# TeensyZE.net
KiCad netlist of a schematic drawn in EAGLE
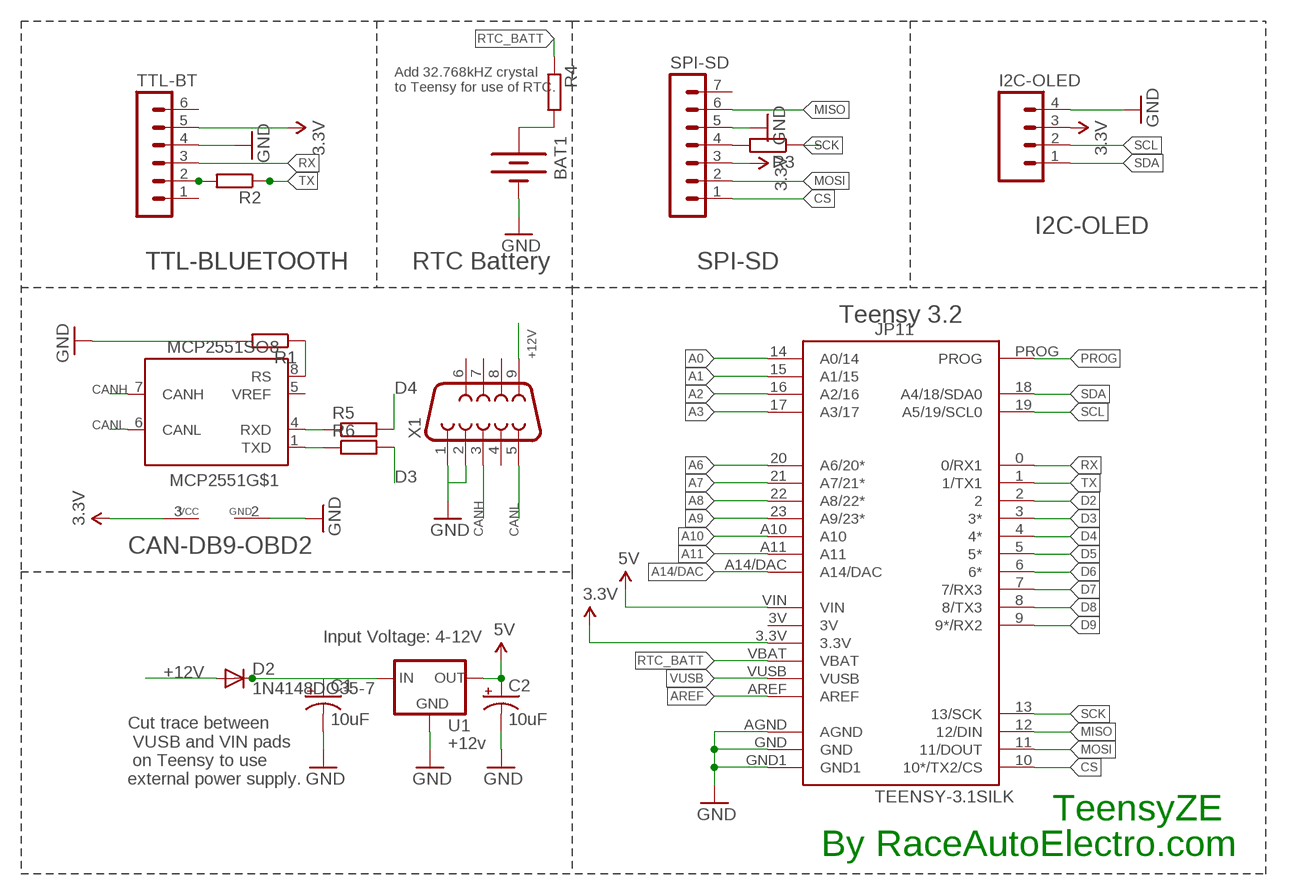
[diagram p0: schematic, sheet 1]

(export (version "E")
  (design (tool "Eeschema 10.0.6"))
  (components
    (comp (ref "BAT1")
      (value "BATTERY12PTH")
      (footprint "eagle-import:BATTCON_12MM_PTH")
      (libsource (lib "eagle-import") (part "BATTERY12PTH"))
    )
    (comp (ref "C1")
      (value "10uF")
      (footprint "eagle-import:CPOL-RADIAL-10UF-25V")
      (libsource (lib "eagle-import") (part "10UF-25V-20%(PTH)"))
    )
    (comp (ref "C2")
      (value "10uF")
      (footprint "eagle-import:CPOL-RADIAL-10UF-25V")
      (libsource (lib "eagle-import") (part "10UF-25V-20%(PTH)"))
    )
    (comp (ref "D2")
      (value "1N4148DO35-7")
      (footprint "eagle-import:DO35-7")
      (libsource (lib "eagle-import") (part "1N4148DO35-7"))
    )
    (comp (ref "I2C-OLED")
      (value "M04PTH")
      (footprint "eagle-import:1X04")
      (libsource (lib "eagle-import") (part "M04PTH"))
    )
    (comp (ref "JP11")
      (value "TEENSY-3.1SILK")
      (footprint "eagle-import:TEENSY-3.1")
      (libsource (lib "eagle-import") (part "TEENSY-3.1SILK"))
    )
    (comp (ref "MCP2551")
      (value "MCP2551SO8")
      (footprint "eagle-import:SO08")
      (libsource (lib "eagle-import") (part "MCP2551SO8"))
    )
    (comp (ref "R1")
      (value "R-EU_R0805")
      (footprint "eagle-import:R0805")
      (libsource (lib "eagle-import") (part "R-EU_R0805"))
    )
    (comp (ref "R2")
      (value "R-EU_R0805")
      (footprint "eagle-import:R0805")
      (libsource (lib "eagle-import") (part "R-EU_R0805"))
    )
    (comp (ref "R3")
      (value "R-EU_R0805")
      (footprint "eagle-import:R0805")
      (libsource (lib "eagle-import") (part "R-EU_R0805"))
    )
    (comp (ref "R4")
      (value "R-EU_R0805")
      (footprint "eagle-import:R0805")
      (libsource (lib "eagle-import") (part "R-EU_R0805"))
    )
    (comp (ref "R5")
      (value "R-EU_R0805")
      (footprint "eagle-import:R0805")
      (libsource (lib "eagle-import") (part "R-EU_R0805"))
    )
    (comp (ref "R6")
      (value "R-EU_R0805")
      (footprint "eagle-import:R0805")
      (libsource (lib "eagle-import") (part "R-EU_R0805"))
    )
    (comp (ref "SPI-SD")
      (value "MA07-1")
      (footprint "eagle-import:MA07-1")
      (libsource (lib "eagle-import") (part "MA07-1"))
    )
    (comp (ref "TTL-BT")
      (value "MA06-1")
      (footprint "eagle-import:MA06-1")
      (libsource (lib "eagle-import") (part "MA06-1"))
    )
    (comp (ref "U1")
      (value "+12v")
      (footprint "eagle-import:TO-252")
      (libsource (lib "eagle-import") (part "V_REG_78XX7812"))
    )
    (comp (ref "X1")
      (value "F09HP")
      (footprint "eagle-import:F09HP")
      (libsource (lib "eagle-import") (part "F09HP"))
    )
  )
  (nets
    (net (code "1") (name "/+12V") (class "Default")
      (node (ref "D2") (pin "A") (pinfunction "A_A") (pintype "passive"))
      (node (ref "X1") (pin "9") (pinfunction "9_9") (pintype "passive"))
    )
    (net (code "2") (name "/CANH") (class "Default")
      (node (ref "MCP2551") (pin "7") (pinfunction "CANH_7") (pintype "bidirectional"))
      (node (ref "X1") (pin "3") (pinfunction "3_3") (pintype "passive"))
    )
    (net (code "3") (name "/CANL") (class "Default")
      (node (ref "MCP2551") (pin "6") (pinfunction "CANL_6") (pintype "bidirectional"))
      (node (ref "X1") (pin "5") (pinfunction "5_5") (pintype "passive"))
    )
    (net (code "4") (name "3.3V") (class "Default")
      (node (ref "I2C-OLED") (pin "3") (pinfunction "3_3") (pintype "passive"))
      (node (ref "JP11") (pin "3.3V") (pinfunction "3.3V_3.3V") (pintype "bidirectional"))
      (node (ref "MCP2551") (pin "3") (pinfunction "VCC_3") (pintype "power_in"))
      (node (ref "SPI-SD") (pin "3") (pinfunction "3_3") (pintype "passive"))
      (node (ref "TTL-BT") (pin "5") (pinfunction "5_5") (pintype "passive"))
    )
    (net (code "5") (name "5V") (class "Default")
      (node (ref "C2") (pin "1") (pinfunction "+_1") (pintype "passive"))
      (node (ref "JP11") (pin "VIN") (pinfunction "VIN_VIN") (pintype "bidirectional"))
      (node (ref "U1") (pin "2") (pinfunction "OUT_2") (pintype "output"))
    )
    (net (code "6") (name "A0") (class "Default")
      (node (ref "JP11") (pin "14") (pinfunction "A0/14_14") (pintype "bidirectional"))
    )
    (net (code "7") (name "A1") (class "Default")
      (node (ref "JP11") (pin "15") (pinfunction "A1/15_15") (pintype "bidirectional"))
    )
    (net (code "8") (name "A2") (class "Default")
      (node (ref "JP11") (pin "16") (pinfunction "A2/16_16") (pintype "bidirectional"))
    )
    (net (code "9") (name "A3") (class "Default")
      (node (ref "JP11") (pin "17") (pinfunction "A3/17_17") (pintype "bidirectional"))
    )
    (net (code "10") (name "A6") (class "Default")
      (node (ref "JP11") (pin "20") (pinfunction "A6/20*_20") (pintype "bidirectional"))
    )
    (net (code "11") (name "A7") (class "Default")
      (node (ref "JP11") (pin "21") (pinfunction "A7/21*_21") (pintype "bidirectional"))
    )
    (net (code "12") (name "A8") (class "Default")
      (node (ref "JP11") (pin "22") (pinfunction "A8/22*_22") (pintype "bidirectional"))
    )
    (net (code "13") (name "A9") (class "Default")
      (node (ref "JP11") (pin "23") (pinfunction "A9/23*_23") (pintype "bidirectional"))
    )
    (net (code "14") (name "A10") (class "Default")
      (node (ref "JP11") (pin "A10") (pinfunction "A10_A10") (pintype "bidirectional"))
    )
    (net (code "15") (name "A11") (class "Default")
      (node (ref "JP11") (pin "A11") (pinfunction "A11_A11") (pintype "bidirectional"))
    )
    (net (code "16") (name "A14{slash}DAC") (class "Default")
      (node (ref "JP11") (pin "A14/DAC") (pinfunction "A14/DAC_A14/DAC") (pintype "bidirectional"))
    )
    (net (code "17") (name "AREF") (class "Default")
      (node (ref "JP11") (pin "AREF") (pinfunction "AREF_AREF") (pintype "bidirectional"))
    )
    (net (code "18") (name "CS") (class "Default")
      (node (ref "JP11") (pin "10") (pinfunction "10*/TX2/CS_10") (pintype "bidirectional"))
      (node (ref "SPI-SD") (pin "1") (pinfunction "1_1") (pintype "passive"))
    )
    (net (code "19") (name "D2") (class "Default")
      (node (ref "JP11") (pin "2") (pinfunction "2_2") (pintype "bidirectional"))
    )
    (net (code "20") (name "D3") (class "Default")
      (node (ref "JP11") (pin "3") (pinfunction "3*_3") (pintype "bidirectional"))
      (node (ref "R6") (pin "2") (pinfunction "2_2") (pintype "passive"))
    )
    (net (code "21") (name "D4") (class "Default")
      (node (ref "JP11") (pin "4") (pinfunction "4*_4") (pintype "bidirectional"))
      (node (ref "R5") (pin "2") (pinfunction "2_2") (pintype "passive"))
    )
    (net (code "22") (name "D5") (class "Default")
      (node (ref "JP11") (pin "5") (pinfunction "5*_5") (pintype "bidirectional"))
    )
    (net (code "23") (name "D6") (class "Default")
      (node (ref "JP11") (pin "6") (pinfunction "6*_6") (pintype "bidirectional"))
    )
    (net (code "24") (name "D7") (class "Default")
      (node (ref "JP11") (pin "7") (pinfunction "7/RX3_7") (pintype "bidirectional"))
    )
    (net (code "25") (name "D8") (class "Default")
      (node (ref "JP11") (pin "8") (pinfunction "8/TX3_8") (pintype "bidirectional"))
    )
    (net (code "26") (name "D9") (class "Default")
      (node (ref "JP11") (pin "9") (pinfunction "9*/RX2_9") (pintype "bidirectional"))
    )
    (net (code "27") (name "GND") (class "Default")
      (node (ref "BAT1") (pin "GND") (pinfunction "-_GND") (pintype "power_in"))
      (node (ref "C1") (pin "2") (pinfunction "-_2") (pintype "passive"))
      (node (ref "C2") (pin "2") (pinfunction "-_2") (pintype "passive"))
      (node (ref "I2C-OLED") (pin "4") (pinfunction "4_4") (pintype "passive"))
      (node (ref "JP11") (pin "AGND") (pinfunction "AGND_AGND") (pintype "bidirectional"))
      (node (ref "JP11") (pin "GND") (pinfunction "GND_GND") (pintype "bidirectional"))
      (node (ref "JP11") (pin "GND1") (pinfunction "GND1_GND1") (pintype "bidirectional"))
      (node (ref "MCP2551") (pin "2") (pinfunction "GND_2") (pintype "power_in"))
      (node (ref "R1") (pin "2") (pinfunction "2_2") (pintype "passive"))
      (node (ref "SPI-SD") (pin "5") (pinfunction "5_5") (pintype "passive"))
      (node (ref "TTL-BT") (pin "4") (pinfunction "4_4") (pintype "passive"))
      (node (ref "U1") (pin "3") (pinfunction "GND_3") (pintype "input"))
      (node (ref "X1") (pin "1") (pinfunction "1_1") (pintype "passive"))
      (node (ref "X1") (pin "2") (pinfunction "2_2") (pintype "passive"))
    )
    (net (code "28") (name "MISO") (class "Default")
      (node (ref "JP11") (pin "12") (pinfunction "12/DIN_12") (pintype "bidirectional"))
      (node (ref "SPI-SD") (pin "6") (pinfunction "6_6") (pintype "passive"))
    )
    (net (code "29") (name "MOSI") (class "Default")
      (node (ref "JP11") (pin "11") (pinfunction "11/DOUT_11") (pintype "bidirectional"))
      (node (ref "SPI-SD") (pin "2") (pinfunction "2_2") (pintype "passive"))
    )
    (net (code "30") (name "Net-(BAT1-+)") (class "Default")
      (node (ref "BAT1") (pin "VCC@1") (pinfunction "+_VCC@1") (pintype "power_in"))
      (node (ref "R4") (pin "2") (pinfunction "2_2") (pintype "passive"))
    )
    (net (code "31") (name "Net-(C1-+)") (class "Default")
      (node (ref "C1") (pin "1") (pinfunction "+_1") (pintype "passive"))
      (node (ref "D2") (pin "C") (pinfunction "C_C") (pintype "passive"))
      (node (ref "U1") (pin "1") (pinfunction "IN_1") (pintype "input"))
    )
    (net (code "32") (name "Net-(MCP2551A-RS)") (class "Default")
      (node (ref "MCP2551") (pin "8") (pinfunction "RS_8") (pintype "bidirectional"))
      (node (ref "R1") (pin "1") (pinfunction "1_1") (pintype "passive"))
    )
    (net (code "33") (name "Net-(MCP2551A-RXD)") (class "Default")
      (node (ref "MCP2551") (pin "4") (pinfunction "RXD_4") (pintype "bidirectional"))
      (node (ref "R5") (pin "1") (pinfunction "1_1") (pintype "passive"))
    )
    (net (code "34") (name "Net-(MCP2551A-TXD)") (class "Default")
      (node (ref "MCP2551") (pin "1") (pinfunction "TXD_1") (pintype "bidirectional"))
      (node (ref "R6") (pin "1") (pinfunction "1_1") (pintype "passive"))
    )
    (net (code "35") (name "Net-(R2-Pad2)") (class "Default")
      (node (ref "R2") (pin "2") (pinfunction "2_2") (pintype "passive"))
      (node (ref "TTL-BT") (pin "2") (pinfunction "2_2") (pintype "passive"))
    )
    (net (code "36") (name "Net-(R3-Pad2)") (class "Default")
      (node (ref "R3") (pin "2") (pinfunction "2_2") (pintype "passive"))
      (node (ref "SPI-SD") (pin "4") (pinfunction "4_4") (pintype "passive"))
    )
    (net (code "37") (name "PROG") (class "Default")
      (node (ref "JP11") (pin "PROG") (pinfunction "PROG_PROG") (pintype "bidirectional"))
    )
    (net (code "38") (name "RTC_BATT") (class "Default")
      (node (ref "JP11") (pin "VBAT") (pinfunction "VBAT_VBAT") (pintype "bidirectional"))
      (node (ref "R4") (pin "1") (pinfunction "1_1") (pintype "passive"))
    )
    (net (code "39") (name "RX") (class "Default")
      (node (ref "JP11") (pin "0") (pinfunction "0/RX1_0") (pintype "bidirectional"))
      (node (ref "TTL-BT") (pin "3") (pinfunction "3_3") (pintype "passive"))
    )
    (net (code "40") (name "SCK") (class "Default")
      (node (ref "JP11") (pin "13") (pinfunction "13/SCK_13") (pintype "bidirectional"))
      (node (ref "R3") (pin "1") (pinfunction "1_1") (pintype "passive"))
    )
    (net (code "41") (name "SCL") (class "Default")
      (node (ref "I2C-OLED") (pin "2") (pinfunction "2_2") (pintype "passive"))
      (node (ref "JP11") (pin "19") (pinfunction "A5/19/SCL0_19") (pintype "bidirectional"))
    )
    (net (code "42") (name "SDA") (class "Default")
      (node (ref "I2C-OLED") (pin "1") (pinfunction "1_1") (pintype "passive"))
      (node (ref "JP11") (pin "18") (pinfunction "A4/18/SDA0_18") (pintype "bidirectional"))
    )
    (net (code "43") (name "TX") (class "Default")
      (node (ref "JP11") (pin "1") (pinfunction "1/TX1_1") (pintype "bidirectional"))
      (node (ref "R2") (pin "1") (pinfunction "1_1") (pintype "passive"))
    )
    (net (code "44") (name "VUSB") (class "Default")
      (node (ref "JP11") (pin "VUSB") (pinfunction "VUSB_VUSB") (pintype "bidirectional"))
    )
    (net (code "45") (name "unconnected-(JP11-Pad3V)") (class "Default")
      (node (ref "JP11") (pin "3V") (pinfunction "3V_3V") (pintype "bidirectional"))
    )
    (net (code "46") (name "unconnected-(MCP2551A-VREF-Pad5)") (class "Default")
      (node (ref "MCP2551") (pin "5") (pinfunction "VREF_5") (pintype "bidirectional"))
    )
    (net (code "47") (name "unconnected-(SPI-SD-Pad7)") (class "Default")
      (node (ref "SPI-SD") (pin "7") (pinfunction "7_7") (pintype "passive"))
    )
    (net (code "48") (name "unconnected-(TTL-BT-Pad1)") (class "Default")
      (node (ref "TTL-BT") (pin "1") (pinfunction "1_1") (pintype "passive"))
    )
    (net (code "49") (name "unconnected-(TTL-BT-Pad6)") (class "Default")
      (node (ref "TTL-BT") (pin "6") (pinfunction "6_6") (pintype "passive"))
    )
    (net (code "50") (name "unconnected-(X1-Pad4)") (class "Default")
      (node (ref "X1") (pin "4") (pinfunction "4_4") (pintype "passive"))
    )
    (net (code "51") (name "unconnected-(X1-Pad6)") (class "Default")
      (node (ref "X1") (pin "6") (pinfunction "6_6") (pintype "passive"))
    )
    (net (code "52") (name "unconnected-(X1-Pad7)") (class "Default")
      (node (ref "X1") (pin "7") (pinfunction "7_7") (pintype "passive"))
    )
    (net (code "53") (name "unconnected-(X1-Pad8)") (class "Default")
      (node (ref "X1") (pin "8") (pinfunction "8_8") (pintype "passive"))
    )
  )
)
